# RPL_MCU_ST.net
KiCad netlist of a schematic drawn in Altium Designer
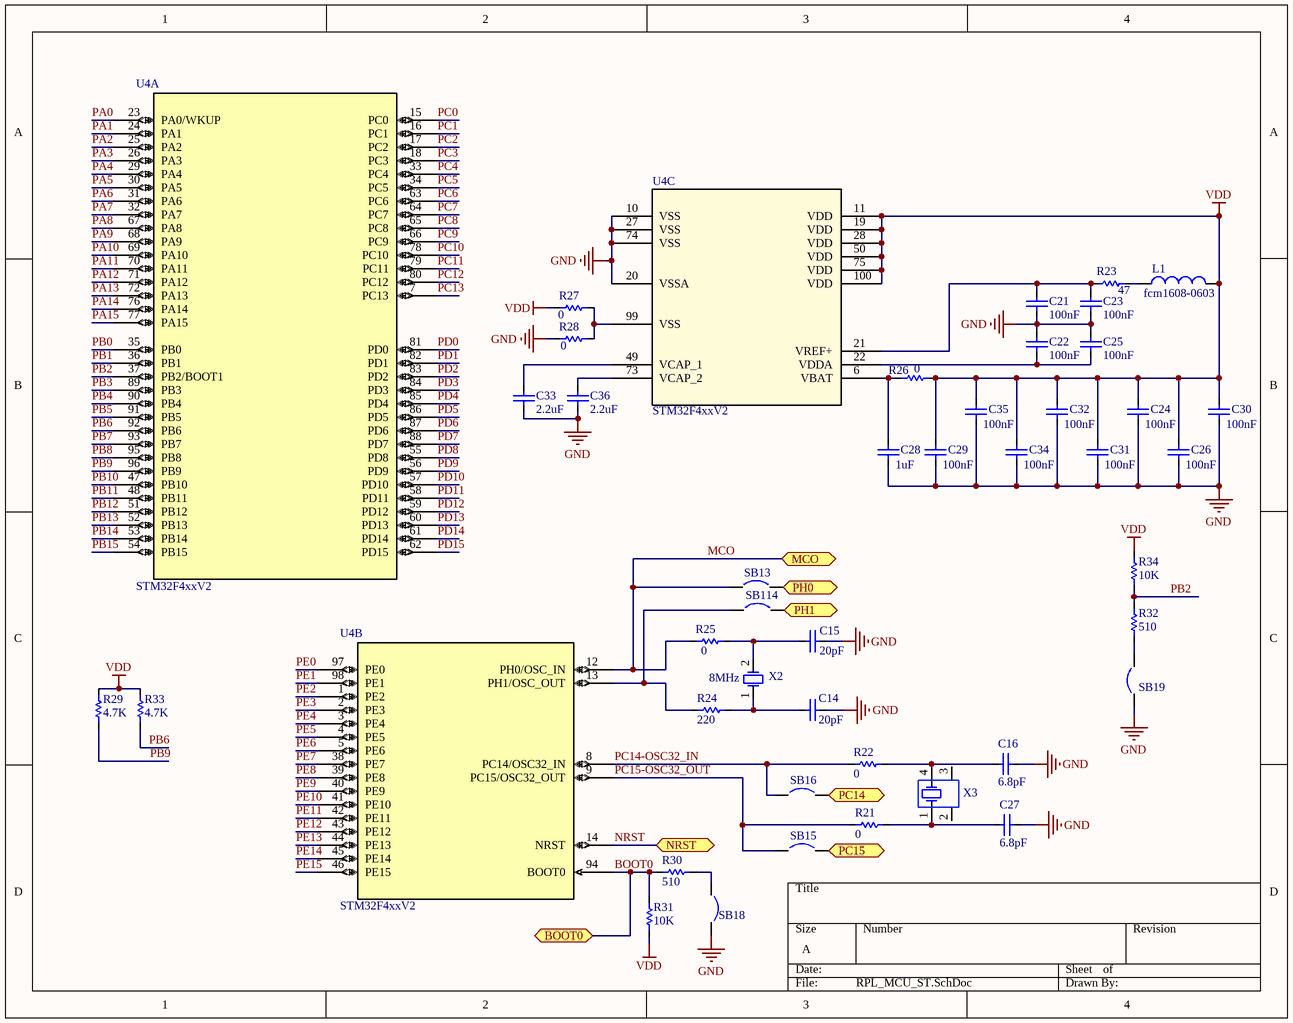
[diagram p0: RPL_MCU_ST.SchDoc]

(export (version "E")
  (design (tool "Eeschema 10.0.6"))
  (components
    (comp (ref "C14")
      (value "20pF")
      (footprint "CC0402KRX7R7BB104:CAPC1005X55N")
      (fields (field (name "Comment") "Cap"))
      (libsource (lib "Generic_Library") (part "Cap"))
    )
    (comp (ref "C15")
      (value "20pF")
      (footprint "CC0402KRX7R7BB104:CAPC1005X55N")
      (fields (field (name "Comment") "Cap"))
      (libsource (lib "Generic_Library") (part "Cap"))
    )
    (comp (ref "C16")
      (value "6.8pF")
      (footprint "CC0402KRX7R7BB104:CAPC1005X55N")
      (fields (field (name "Comment") "Cap"))
      (libsource (lib "Generic_Library") (part "Cap"))
    )
    (comp (ref "C21")
      (value "100nF")
      (footprint "CC0402KRX7R7BB104:CAPC1005X55N")
      (fields (field (name "Comment") "Cap"))
      (libsource (lib "Generic_Library") (part "Cap"))
    )
    (comp (ref "C22")
      (value "100nF")
      (footprint "CC0402KRX7R7BB104:CAPC1005X55N")
      (fields (field (name "Comment") "Cap"))
      (libsource (lib "Generic_Library") (part "Cap"))
    )
    (comp (ref "C23")
      (value "100nF")
      (footprint "CC0402KRX7R7BB104:CAPC1005X55N")
      (fields (field (name "Comment") "Cap"))
      (libsource (lib "Generic_Library") (part "Cap"))
    )
    (comp (ref "C24")
      (value "100nF")
      (footprint "CC0402KRX7R7BB104:CAPC1005X55N")
      (fields (field (name "Comment") "Cap"))
      (libsource (lib "Generic_Library") (part "Cap"))
    )
    (comp (ref "C25")
      (value "100nF")
      (footprint "CC0402KRX7R7BB104:CAPC1005X55N")
      (fields (field (name "Comment") "Cap"))
      (libsource (lib "Generic_Library") (part "Cap"))
    )
    (comp (ref "C26")
      (value "100nF")
      (footprint "CC0402KRX7R7BB104:CAPC1005X55N")
      (fields (field (name "Comment") "Cap"))
      (libsource (lib "Generic_Library") (part "Cap"))
    )
    (comp (ref "C27")
      (value "6.8pF")
      (footprint "CC0402KRX7R7BB104:CAPC1005X55N")
      (fields (field (name "Comment") "Cap"))
      (libsource (lib "Generic_Library") (part "Cap"))
    )
    (comp (ref "C28")
      (value "1uF")
      (footprint "CC0402KRX7R7BB104:CAPC1005X55N")
      (fields (field (name "Comment") "Cap"))
      (libsource (lib "Generic_Library") (part "Cap"))
    )
    (comp (ref "C29")
      (value "100nF")
      (footprint "CC0402KRX7R7BB104:CAPC1005X55N")
      (fields (field (name "Comment") "Cap"))
      (libsource (lib "Generic_Library") (part "Cap"))
    )
    (comp (ref "C30")
      (value "100nF")
      (footprint "CC0402KRX7R7BB104:CAPC1005X55N")
      (fields (field (name "Comment") "Cap"))
      (libsource (lib "Generic_Library") (part "Cap"))
    )
    (comp (ref "C31")
      (value "100nF")
      (footprint "CC0402KRX7R7BB104:CAPC1005X55N")
      (fields (field (name "Comment") "Cap"))
      (libsource (lib "Generic_Library") (part "Cap"))
    )
    (comp (ref "C32")
      (value "100nF")
      (footprint "CC0402KRX7R7BB104:CAPC1005X55N")
      (fields (field (name "Comment") "Cap"))
      (libsource (lib "Generic_Library") (part "Cap"))
    )
    (comp (ref "C33")
      (value "2.2uF")
      (footprint "CC0402KRX7R7BB104:CAPC1005X55N")
      (fields (field (name "Comment") "Cap"))
      (libsource (lib "Generic_Library") (part "Cap"))
    )
    (comp (ref "C34")
      (value "100nF")
      (footprint "CC0402KRX7R7BB104:CAPC1005X55N")
      (fields (field (name "Comment") "Cap"))
      (libsource (lib "Generic_Library") (part "Cap"))
    )
    (comp (ref "C35")
      (value "100nF")
      (footprint "CC0402KRX7R7BB104:CAPC1005X55N")
      (fields (field (name "Comment") "Cap"))
      (libsource (lib "Generic_Library") (part "Cap"))
    )
    (comp (ref "C36")
      (value "2.2uF")
      (footprint "CC0402KRX7R7BB104:CAPC1005X55N")
      (fields (field (name "Comment") "Cap"))
      (libsource (lib "Generic_Library") (part "Cap"))
    )
    (comp (ref "L1") (value "fcm1608-0603") (libsource (lib "Generic_Library") (part "Inductor")))
    (comp (ref "R21")
      (value "0")
      (footprint "RC0603JR-070RL:0603")
      (fields (field (name "Comment") "Res"))
      (libsource (lib "Generic_Library") (part "Res"))
    )
    (comp (ref "R22")
      (value "0")
      (footprint "RC0603JR-070RL:0603")
      (fields (field (name "Comment") "Res"))
      (libsource (lib "Generic_Library") (part "Res"))
    )
    (comp (ref "R23")
      (value "47")
      (fields (field (name "Comment") "Res"))
      (libsource (lib "Generic_Library") (part "Res"))
    )
    (comp (ref "R24")
      (value "220")
      (footprint "RC0603JR-070RL:0603")
      (fields (field (name "Comment") "Res"))
      (libsource (lib "Generic_Library") (part "Res"))
    )
    (comp (ref "R25")
      (value "0")
      (footprint "RC0603JR-070RL:0603")
      (fields (field (name "Comment") "Res"))
      (libsource (lib "Generic_Library") (part "Res"))
    )
    (comp (ref "R26")
      (value "0")
      (footprint "RC0603JR-070RL:0603")
      (fields (field (name "Comment") "Res"))
      (libsource (lib "Generic_Library") (part "Res"))
    )
    (comp (ref "R27")
      (value "0")
      (footprint "RC0603JR-070RL:0603")
      (fields (field (name "Comment") "Res"))
      (libsource (lib "Generic_Library") (part "Res"))
    )
    (comp (ref "R28")
      (value "0")
      (footprint "RC0603JR-070RL:0603")
      (fields (field (name "Comment") "Res"))
      (libsource (lib "Generic_Library") (part "Res"))
    )
    (comp (ref "R29")
      (value "4.7K")
      (footprint "RC0603JR-070RL:0603")
      (fields (field (name "Comment") "Res"))
      (libsource (lib "Generic_Library") (part "Res"))
    )
    (comp (ref "R30")
      (value "510")
      (footprint "RC0603JR-070RL:0603")
      (fields (field (name "Comment") "Res"))
      (libsource (lib "Generic_Library") (part "Res"))
    )
    (comp (ref "R31")
      (value "10K")
      (footprint "RC0603JR-070RL:0603")
      (fields (field (name "Comment") "Res"))
      (libsource (lib "Generic_Library") (part "Res"))
    )
    (comp (ref "R32")
      (value "510")
      (footprint "RC0603JR-070RL:0603")
      (fields (field (name "Comment") "Res"))
      (libsource (lib "Generic_Library") (part "Res"))
    )
    (comp (ref "R33")
      (value "4.7K")
      (footprint "RC0603JR-070RL:0603")
      (fields (field (name "Comment") "Res"))
      (libsource (lib "Generic_Library") (part "Res"))
    )
    (comp (ref "R34")
      (value "10K")
      (footprint "RC0603JR-070RL:0603")
      (fields (field (name "Comment") "Res"))
      (libsource (lib "Generic_Library") (part "Res"))
    )
    (comp (ref "SB13") (value "Circuit Breaker") (libsource (lib "Generic_Library") (part "Circuit Breaker")))
    (comp (ref "SB15") (value "Circuit Breaker") (libsource (lib "Generic_Library") (part "Circuit Breaker")))
    (comp (ref "SB16") (value "Circuit Breaker") (libsource (lib "Generic_Library") (part "Circuit Breaker")))
    (comp (ref "SB18") (value "Circuit Breaker") (libsource (lib "Generic_Library") (part "Circuit Breaker")))
    (comp (ref "SB19") (value "Circuit Breaker") (libsource (lib "Generic_Library") (part "Circuit Breaker")))
    (comp (ref "SB114")
      (value "Circuit Breaker")
      (libsource (lib "Generic_Library") (part "Circuit Breaker"))
    )
    (comp (ref "U4")
      (value "STM32F4xxV2")
      (footprint "STM32F4xxV2:LQFP100-14x14mm")
      (description "Imported")
      (fields
        (field (name "MANUFACTURER_PART_NUMBER") "stm32f4xxv2")
        (field (name "COPYRIGHT") "Copyright (C) 2016 Accelerated Designs. All rights reserved")
      )
      (libsource (lib "Generic_Library") (part "STM32F4xxV2"))
    )
    (comp (ref "X2")
      (value "8MHz")
      (fields (field (name "Comment") "XTAL"))
      (libsource (lib "Generic_Library") (part "XTAL"))
    )
    (comp (ref "X3") (value "XTAL_4pin") (libsource (lib "Generic_Library") (part "XTAL_4pin")))
  )
  (nets
    (net (code "1") (name "/BOOT0") (class "Default")
      (node (ref "R30") (pin "1") (pinfunction "1_1") (pintype "passive"))
      (node (ref "R31") (pin "1") (pinfunction "1_1") (pintype "passive"))
      (node (ref "U4") (pin "94") (pinfunction "BOOT0_94") (pintype "input"))
    )
    (net (code "2") (name "/MCO") (class "Default")
      (node (ref "R25") (pin "1") (pinfunction "1_1") (pintype "passive"))
      (node (ref "SB13") (pin "1") (pinfunction "1_1") (pintype "passive"))
      (node (ref "U4") (pin "12") (pinfunction "PH0/OSC_IN_12") (pintype "bidirectional"))
    )
    (net (code "3") (name "/NRST") (class "Default")
      (node (ref "U4") (pin "14") (pinfunction "NRST_14") (pintype "bidirectional"))
    )
    (net (code "4") (name "/PA0") (class "Default")
      (node (ref "U4") (pin "23") (pinfunction "PA0/WKUP_23") (pintype "bidirectional"))
    )
    (net (code "5") (name "/PA1") (class "Default")
      (node (ref "U4") (pin "24") (pinfunction "PA1_24") (pintype "bidirectional"))
    )
    (net (code "6") (name "/PA2") (class "Default")
      (node (ref "U4") (pin "25") (pinfunction "PA2_25") (pintype "bidirectional"))
    )
    (net (code "7") (name "/PA3") (class "Default")
      (node (ref "U4") (pin "26") (pinfunction "PA3_26") (pintype "bidirectional"))
    )
    (net (code "8") (name "/PA4") (class "Default")
      (node (ref "U4") (pin "29") (pinfunction "PA4_29") (pintype "bidirectional"))
    )
    (net (code "9") (name "/PA5") (class "Default")
      (node (ref "U4") (pin "30") (pinfunction "PA5_30") (pintype "bidirectional"))
    )
    (net (code "10") (name "/PA6") (class "Default")
      (node (ref "U4") (pin "31") (pinfunction "PA6_31") (pintype "bidirectional"))
    )
    (net (code "11") (name "/PA7") (class "Default")
      (node (ref "U4") (pin "32") (pinfunction "PA7_32") (pintype "bidirectional"))
    )
    (net (code "12") (name "/PA8") (class "Default")
      (node (ref "U4") (pin "67") (pinfunction "PA8_67") (pintype "bidirectional"))
    )
    (net (code "13") (name "/PA9") (class "Default")
      (node (ref "U4") (pin "68") (pinfunction "PA9_68") (pintype "bidirectional"))
    )
    (net (code "14") (name "/PA10") (class "Default")
      (node (ref "U4") (pin "69") (pinfunction "PA10_69") (pintype "bidirectional"))
    )
    (net (code "15") (name "/PA11") (class "Default")
      (node (ref "U4") (pin "70") (pinfunction "PA11_70") (pintype "bidirectional"))
    )
    (net (code "16") (name "/PA12") (class "Default")
      (node (ref "U4") (pin "71") (pinfunction "PA12_71") (pintype "bidirectional"))
    )
    (net (code "17") (name "/PA13") (class "Default")
      (node (ref "U4") (pin "72") (pinfunction "PA13_72") (pintype "bidirectional"))
    )
    (net (code "18") (name "/PA14") (class "Default")
      (node (ref "U4") (pin "76") (pinfunction "PA14_76") (pintype "bidirectional"))
    )
    (net (code "19") (name "/PA15") (class "Default")
      (node (ref "U4") (pin "77") (pinfunction "PA15_77") (pintype "bidirectional"))
    )
    (net (code "20") (name "/PB0") (class "Default")
      (node (ref "U4") (pin "35") (pinfunction "PB0_35") (pintype "bidirectional"))
    )
    (net (code "21") (name "/PB1") (class "Default")
      (node (ref "U4") (pin "36") (pinfunction "PB1_36") (pintype "bidirectional"))
    )
    (net (code "22") (name "/PB2") (class "Default")
      (node (ref "R32") (pin "2") (pinfunction "2_2") (pintype "passive"))
      (node (ref "R34") (pin "1") (pinfunction "1_1") (pintype "passive"))
      (node (ref "U4") (pin "37") (pinfunction "PB2/BOOT1_37") (pintype "bidirectional"))
    )
    (net (code "23") (name "/PB3") (class "Default")
      (node (ref "U4") (pin "89") (pinfunction "PB3_89") (pintype "bidirectional"))
    )
    (net (code "24") (name "/PB4") (class "Default")
      (node (ref "U4") (pin "90") (pinfunction "PB4_90") (pintype "bidirectional"))
    )
    (net (code "25") (name "/PB5") (class "Default")
      (node (ref "U4") (pin "91") (pinfunction "PB5_91") (pintype "bidirectional"))
    )
    (net (code "26") (name "/PB6") (class "Default")
      (node (ref "R33") (pin "1") (pinfunction "1_1") (pintype "passive"))
      (node (ref "U4") (pin "92") (pinfunction "PB6_92") (pintype "bidirectional"))
    )
    (net (code "27") (name "/PB7") (class "Default")
      (node (ref "U4") (pin "93") (pinfunction "PB7_93") (pintype "bidirectional"))
    )
    (net (code "28") (name "/PB8") (class "Default")
      (node (ref "U4") (pin "95") (pinfunction "PB8_95") (pintype "bidirectional"))
    )
    (net (code "29") (name "/PB9") (class "Default")
      (node (ref "R29") (pin "1") (pinfunction "1_1") (pintype "passive"))
      (node (ref "U4") (pin "96") (pinfunction "PB9_96") (pintype "bidirectional"))
    )
    (net (code "30") (name "/PB10") (class "Default")
      (node (ref "U4") (pin "47") (pinfunction "PB10_47") (pintype "bidirectional"))
    )
    (net (code "31") (name "/PB11") (class "Default")
      (node (ref "U4") (pin "48") (pinfunction "PB11_48") (pintype "bidirectional"))
    )
    (net (code "32") (name "/PB12") (class "Default")
      (node (ref "U4") (pin "51") (pinfunction "PB12_51") (pintype "bidirectional"))
    )
    (net (code "33") (name "/PB13") (class "Default")
      (node (ref "U4") (pin "52") (pinfunction "PB13_52") (pintype "bidirectional"))
    )
    (net (code "34") (name "/PB14") (class "Default")
      (node (ref "U4") (pin "53") (pinfunction "PB14_53") (pintype "bidirectional"))
    )
    (net (code "35") (name "/PB15") (class "Default")
      (node (ref "U4") (pin "54") (pinfunction "PB15_54") (pintype "bidirectional"))
    )
    (net (code "36") (name "/PC0") (class "Default")
      (node (ref "U4") (pin "15") (pinfunction "PC0_15") (pintype "bidirectional"))
    )
    (net (code "37") (name "/PC1") (class "Default")
      (node (ref "U4") (pin "16") (pinfunction "PC1_16") (pintype "bidirectional"))
    )
    (net (code "38") (name "/PC2") (class "Default")
      (node (ref "U4") (pin "17") (pinfunction "PC2_17") (pintype "bidirectional"))
    )
    (net (code "39") (name "/PC3") (class "Default")
      (node (ref "U4") (pin "18") (pinfunction "PC3_18") (pintype "bidirectional"))
    )
    (net (code "40") (name "/PC4") (class "Default")
      (node (ref "U4") (pin "33") (pinfunction "PC4_33") (pintype "bidirectional"))
    )
    (net (code "41") (name "/PC5") (class "Default")
      (node (ref "U4") (pin "34") (pinfunction "PC5_34") (pintype "bidirectional"))
    )
    (net (code "42") (name "/PC6") (class "Default")
      (node (ref "U4") (pin "63") (pinfunction "PC6_63") (pintype "bidirectional"))
    )
    (net (code "43") (name "/PC7") (class "Default")
      (node (ref "U4") (pin "64") (pinfunction "PC7_64") (pintype "bidirectional"))
    )
    (net (code "44") (name "/PC8") (class "Default")
      (node (ref "U4") (pin "65") (pinfunction "PC8_65") (pintype "bidirectional"))
    )
    (net (code "45") (name "/PC9") (class "Default")
      (node (ref "U4") (pin "66") (pinfunction "PC9_66") (pintype "bidirectional"))
    )
    (net (code "46") (name "/PC10") (class "Default")
      (node (ref "U4") (pin "78") (pinfunction "PC10_78") (pintype "bidirectional"))
    )
    (net (code "47") (name "/PC11") (class "Default")
      (node (ref "U4") (pin "79") (pinfunction "PC11_79") (pintype "bidirectional"))
    )
    (net (code "48") (name "/PC12") (class "Default")
      (node (ref "U4") (pin "80") (pinfunction "PC12_80") (pintype "bidirectional"))
    )
    (net (code "49") (name "/PC13") (class "Default")
      (node (ref "U4") (pin "7") (pinfunction "PC13_7") (pintype "bidirectional"))
    )
    (net (code "50") (name "/PC14") (class "Default")
      (node (ref "SB16") (pin "2") (pinfunction "2_2") (pintype "passive"))
    )
    (net (code "51") (name "/PC14-OSC32_IN") (class "Default")
      (node (ref "R22") (pin "1") (pinfunction "1_1") (pintype "passive"))
      (node (ref "SB16") (pin "1") (pinfunction "1_1") (pintype "passive"))
      (node (ref "U4") (pin "8") (pinfunction "PC14/OSC32_IN_8") (pintype "bidirectional"))
    )
    (net (code "52") (name "/PC15") (class "Default")
      (node (ref "SB15") (pin "2") (pinfunction "2_2") (pintype "passive"))
    )
    (net (code "53") (name "/PC15-OSC32_OUT") (class "Default")
      (node (ref "R21") (pin "1") (pinfunction "1_1") (pintype "passive"))
      (node (ref "SB15") (pin "1") (pinfunction "1_1") (pintype "passive"))
      (node (ref "U4") (pin "9") (pinfunction "PC15/OSC32_OUT_9") (pintype "bidirectional"))
    )
    (net (code "54") (name "/PD0") (class "Default")
      (node (ref "U4") (pin "81") (pinfunction "PD0_81") (pintype "bidirectional"))
    )
    (net (code "55") (name "/PD1") (class "Default")
      (node (ref "U4") (pin "82") (pinfunction "PD1_82") (pintype "bidirectional"))
    )
    (net (code "56") (name "/PD2") (class "Default")
      (node (ref "U4") (pin "83") (pinfunction "PD2_83") (pintype "bidirectional"))
    )
    (net (code "57") (name "/PD3") (class "Default")
      (node (ref "U4") (pin "84") (pinfunction "PD3_84") (pintype "bidirectional"))
    )
    (net (code "58") (name "/PD4") (class "Default")
      (node (ref "U4") (pin "85") (pinfunction "PD4_85") (pintype "bidirectional"))
    )
    (net (code "59") (name "/PD5") (class "Default")
      (node (ref "U4") (pin "86") (pinfunction "PD5_86") (pintype "bidirectional"))
    )
    (net (code "60") (name "/PD6") (class "Default")
      (node (ref "U4") (pin "87") (pinfunction "PD6_87") (pintype "bidirectional"))
    )
    (net (code "61") (name "/PD7") (class "Default")
      (node (ref "U4") (pin "88") (pinfunction "PD7_88") (pintype "bidirectional"))
    )
    (net (code "62") (name "/PD8") (class "Default")
      (node (ref "U4") (pin "55") (pinfunction "PD8_55") (pintype "bidirectional"))
    )
    (net (code "63") (name "/PD9") (class "Default")
      (node (ref "U4") (pin "56") (pinfunction "PD9_56") (pintype "bidirectional"))
    )
    (net (code "64") (name "/PD10") (class "Default")
      (node (ref "U4") (pin "57") (pinfunction "PD10_57") (pintype "bidirectional"))
    )
    (net (code "65") (name "/PD11") (class "Default")
      (node (ref "U4") (pin "58") (pinfunction "PD11_58") (pintype "bidirectional"))
    )
    (net (code "66") (name "/PD12") (class "Default")
      (node (ref "U4") (pin "59") (pinfunction "PD12_59") (pintype "bidirectional"))
    )
    (net (code "67") (name "/PD13") (class "Default")
      (node (ref "U4") (pin "60") (pinfunction "PD13_60") (pintype "bidirectional"))
    )
    (net (code "68") (name "/PD14") (class "Default")
      (node (ref "U4") (pin "61") (pinfunction "PD14_61") (pintype "bidirectional"))
    )
    (net (code "69") (name "/PD15") (class "Default")
      (node (ref "U4") (pin "62") (pinfunction "PD15_62") (pintype "bidirectional"))
    )
    (net (code "70") (name "/PE0") (class "Default")
      (node (ref "U4") (pin "97") (pinfunction "PE0_97") (pintype "bidirectional"))
    )
    (net (code "71") (name "/PE1") (class "Default")
      (node (ref "U4") (pin "98") (pinfunction "PE1_98") (pintype "bidirectional"))
    )
    (net (code "72") (name "/PE2") (class "Default")
      (node (ref "U4") (pin "1") (pinfunction "PE2_1") (pintype "bidirectional"))
    )
    (net (code "73") (name "/PE3") (class "Default")
      (node (ref "U4") (pin "2") (pinfunction "PE3_2") (pintype "bidirectional"))
    )
    (net (code "74") (name "/PE4") (class "Default")
      (node (ref "U4") (pin "3") (pinfunction "PE4_3") (pintype "bidirectional"))
    )
    (net (code "75") (name "/PE5") (class "Default")
      (node (ref "U4") (pin "4") (pinfunction "PE5_4") (pintype "bidirectional"))
    )
    (net (code "76") (name "/PE6") (class "Default")
      (node (ref "U4") (pin "5") (pinfunction "PE6_5") (pintype "bidirectional"))
    )
    (net (code "77") (name "/PE7") (class "Default")
      (node (ref "U4") (pin "38") (pinfunction "PE7_38") (pintype "bidirectional"))
    )
    (net (code "78") (name "/PE8") (class "Default")
      (node (ref "U4") (pin "39") (pinfunction "PE8_39") (pintype "bidirectional"))
    )
    (net (code "79") (name "/PE9") (class "Default")
      (node (ref "U4") (pin "40") (pinfunction "PE9_40") (pintype "bidirectional"))
    )
    (net (code "80") (name "/PE10") (class "Default")
      (node (ref "U4") (pin "41") (pinfunction "PE10_41") (pintype "bidirectional"))
    )
    (net (code "81") (name "/PE11") (class "Default")
      (node (ref "U4") (pin "42") (pinfunction "PE11_42") (pintype "bidirectional"))
    )
    (net (code "82") (name "/PE12") (class "Default")
      (node (ref "U4") (pin "43") (pinfunction "PE12_43") (pintype "bidirectional"))
    )
    (net (code "83") (name "/PE13") (class "Default")
      (node (ref "U4") (pin "44") (pinfunction "PE13_44") (pintype "bidirectional"))
    )
    (net (code "84") (name "/PE14") (class "Default")
      (node (ref "U4") (pin "45") (pinfunction "PE14_45") (pintype "bidirectional"))
    )
    (net (code "85") (name "/PE15") (class "Default")
      (node (ref "U4") (pin "46") (pinfunction "PE15_46") (pintype "bidirectional"))
    )
    (net (code "86") (name "/PH0") (class "Default")
      (node (ref "SB13") (pin "2") (pinfunction "2_2") (pintype "passive"))
    )
    (net (code "87") (name "/PH1") (class "Default")
      (node (ref "SB114") (pin "2") (pinfunction "2_2") (pintype "passive"))
    )
    (net (code "88") (name "GND") (class "Default")
      (node (ref "C14") (pin "2") (pinfunction "2_2") (pintype "passive"))
      (node (ref "C15") (pin "2") (pinfunction "2_2") (pintype "passive"))
      (node (ref "C16") (pin "2") (pinfunction "2_2") (pintype "passive"))
      (node (ref "C21") (pin "1") (pinfunction "1_1") (pintype "passive"))
      (node (ref "C22") (pin "2") (pinfunction "2_2") (pintype "passive"))
      (node (ref "C23") (pin "1") (pinfunction "1_1") (pintype "passive"))
      (node (ref "C24") (pin "1") (pinfunction "1_1") (pintype "passive"))
      (node (ref "C25") (pin "2") (pinfunction "2_2") (pintype "passive"))
      (node (ref "C26") (pin "1") (pinfunction "1_1") (pintype "passive"))
      (node (ref "C27") (pin "2") (pinfunction "2_2") (pintype "passive"))
      (node (ref "C28") (pin "1") (pinfunction "1_1") (pintype "passive"))
      (node (ref "C29") (pin "1") (pinfunction "1_1") (pintype "passive"))
      (node (ref "C30") (pin "1") (pinfunction "1_1") (pintype "passive"))
      (node (ref "C31") (pin "1") (pinfunction "1_1") (pintype "passive"))
      (node (ref "C32") (pin "1") (pinfunction "1_1") (pintype "passive"))
      (node (ref "C33") (pin "1") (pinfunction "1_1") (pintype "passive"))
      (node (ref "C34") (pin "1") (pinfunction "1_1") (pintype "passive"))
      (node (ref "C35") (pin "1") (pinfunction "1_1") (pintype "passive"))
      (node (ref "C36") (pin "1") (pinfunction "1_1") (pintype "passive"))
      (node (ref "R28") (pin "1") (pinfunction "1_1") (pintype "passive"))
      (node (ref "SB18") (pin "2") (pinfunction "2_2") (pintype "passive"))
      (node (ref "SB19") (pin "1") (pinfunction "1_1") (pintype "passive"))
      (node (ref "U4") (pin "10") (pinfunction "VSS_10") (pintype "power_in"))
      (node (ref "U4") (pin "20") (pinfunction "VSSA_20") (pintype "power_in"))
      (node (ref "U4") (pin "27") (pinfunction "VSS_27") (pintype "power_in"))
      (node (ref "U4") (pin "74") (pinfunction "VSS_74") (pintype "power_in"))
    )
    (net (code "89") (name "Net-(C16-Pad1)") (class "Default")
      (node (ref "C16") (pin "1") (pinfunction "1_1") (pintype "passive"))
      (node (ref "R22") (pin "2") (pinfunction "2_2") (pintype "passive"))
      (node (ref "X3") (pin "4") (pinfunction "OSC2_4") (pintype "passive"))
    )
    (net (code "90") (name "Net-(L1-Pad1)") (class "Default")
      (node (ref "L1") (pin "1") (pinfunction "1_1") (pintype "passive"))
      (node (ref "R23") (pin "2") (pinfunction "2_2") (pintype "passive"))
    )
    (net (code "91") (name "Net-(R27-Pad2)") (class "Default")
      (node (ref "R27") (pin "2") (pinfunction "2_2") (pintype "passive"))
      (node (ref "R28") (pin "2") (pinfunction "2_2") (pintype "passive"))
      (node (ref "U4") (pin "99") (pinfunction "VSS_99") (pintype "power_in"))
    )
    (net (code "92") (name "Net-(R30-Pad2)") (class "Default")
      (node (ref "R30") (pin "2") (pinfunction "2_2") (pintype "passive"))
      (node (ref "SB18") (pin "1") (pinfunction "1_1") (pintype "passive"))
    )
    (net (code "93") (name "Net-(R32-Pad1)") (class "Default")
      (node (ref "R32") (pin "1") (pinfunction "1_1") (pintype "passive"))
      (node (ref "SB19") (pin "2") (pinfunction "2_2") (pintype "passive"))
    )
    (net (code "94") (name "Net-(U4B-PH1{slash}OSC_OUT)") (class "Default")
      (node (ref "R24") (pin "1") (pinfunction "1_1") (pintype "passive"))
      (node (ref "SB114") (pin "1") (pinfunction "1_1") (pintype "passive"))
      (node (ref "U4") (pin "13") (pinfunction "PH1/OSC_OUT_13") (pintype "bidirectional"))
    )
    (net (code "95") (name "Net-(U4C-VBAT)") (class "Default")
      (node (ref "C28") (pin "2") (pinfunction "2_2") (pintype "passive"))
      (node (ref "R26") (pin "1") (pinfunction "1_1") (pintype "passive"))
      (node (ref "U4") (pin "6") (pinfunction "VBAT_6") (pintype "power_in"))
    )
    (net (code "96") (name "Net-(U4C-VCAP_1)") (class "Default")
      (node (ref "C33") (pin "2") (pinfunction "2_2") (pintype "passive"))
      (node (ref "U4") (pin "49") (pinfunction "VCAP_1_49") (pintype "power_in"))
    )
    (net (code "97") (name "Net-(U4C-VCAP_2)") (class "Default")
      (node (ref "C36") (pin "2") (pinfunction "2_2") (pintype "passive"))
      (node (ref "U4") (pin "73") (pinfunction "VCAP_2_73") (pintype "power_in"))
    )
    (net (code "98") (name "Net-(U4C-VDDA)") (class "Default")
      (node (ref "C22") (pin "1") (pinfunction "1_1") (pintype "passive"))
      (node (ref "C25") (pin "1") (pinfunction "1_1") (pintype "passive"))
      (node (ref "U4") (pin "22") (pinfunction "VDDA_22") (pintype "power_in"))
    )
    (net (code "99") (name "Net-(U4C-VREF+)") (class "Default")
      (node (ref "C21") (pin "2") (pinfunction "2_2") (pintype "passive"))
      (node (ref "C23") (pin "2") (pinfunction "2_2") (pintype "passive"))
      (node (ref "R23") (pin "1") (pinfunction "1_1") (pintype "passive"))
      (node (ref "U4") (pin "21") (pinfunction "VREF+_21") (pintype "power_in"))
    )
    (net (code "100") (name "Net-(X2-OSC1)") (class "Default")
      (node (ref "C14") (pin "1") (pinfunction "1_1") (pintype "passive"))
      (node (ref "R24") (pin "2") (pinfunction "2_2") (pintype "passive"))
      (node (ref "X2") (pin "1") (pinfunction "OSC1_1") (pintype "passive"))
    )
    (net (code "101") (name "Net-(X2-OSC2)") (class "Default")
      (node (ref "C15") (pin "1") (pinfunction "1_1") (pintype "passive"))
      (node (ref "R25") (pin "2") (pinfunction "2_2") (pintype "passive"))
      (node (ref "X2") (pin "2") (pinfunction "OSC2_2") (pintype "passive"))
    )
    (net (code "102") (name "Net-(X3-OSC1)") (class "Default")
      (node (ref "C27") (pin "1") (pinfunction "1_1") (pintype "passive"))
      (node (ref "R21") (pin "2") (pinfunction "2_2") (pintype "passive"))
      (node (ref "X3") (pin "1") (pinfunction "OSC1_1") (pintype "passive"))
    )
    (net (code "103") (name "VDD") (class "Default")
      (node (ref "C24") (pin "2") (pinfunction "2_2") (pintype "passive"))
      (node (ref "C26") (pin "2") (pinfunction "2_2") (pintype "passive"))
      (node (ref "C29") (pin "2") (pinfunction "2_2") (pintype "passive"))
      (node (ref "C30") (pin "2") (pinfunction "2_2") (pintype "passive"))
      (node (ref "C31") (pin "2") (pinfunction "2_2") (pintype "passive"))
      (node (ref "C32") (pin "2") (pinfunction "2_2") (pintype "passive"))
      (node (ref "C34") (pin "2") (pinfunction "2_2") (pintype "passive"))
      (node (ref "C35") (pin "2") (pinfunction "2_2") (pintype "passive"))
      (node (ref "L1") (pin "2") (pinfunction "2_2") (pintype "passive"))
      (node (ref "R26") (pin "2") (pinfunction "2_2") (pintype "passive"))
      (node (ref "R27") (pin "1") (pinfunction "1_1") (pintype "passive"))
      (node (ref "R29") (pin "2") (pinfunction "2_2") (pintype "passive"))
      (node (ref "R31") (pin "2") (pinfunction "2_2") (pintype "passive"))
      (node (ref "R33") (pin "2") (pinfunction "2_2") (pintype "passive"))
      (node (ref "R34") (pin "2") (pinfunction "2_2") (pintype "passive"))
      (node (ref "U4") (pin "100") (pinfunction "VDD_100") (pintype "power_in"))
      (node (ref "U4") (pin "11") (pinfunction "VDD_11") (pintype "power_in"))
      (node (ref "U4") (pin "19") (pinfunction "VDD_19") (pintype "power_in"))
      (node (ref "U4") (pin "28") (pinfunction "VDD_28") (pintype "power_in"))
      (node (ref "U4") (pin "50") (pinfunction "VDD_50") (pintype "power_in"))
      (node (ref "U4") (pin "75") (pinfunction "VDD_75") (pintype "power_in"))
    )
    (net (code "104") (name "unconnected-(X3-OSC2-Pad2)") (class "Default")
      (node (ref "X3") (pin "2") (pinfunction "OSC2_2") (pintype "passive"))
    )
    (net (code "105") (name "unconnected-(X3-OSC3-Pad3)") (class "Default")
      (node (ref "X3") (pin "3") (pinfunction "OSC3_3") (pintype "passive"))
    )
  )
)
